# DIGITAL_40G_ACCELEROMETER_REV_1.net
KiCad netlist of a schematic drawn in EAGLE
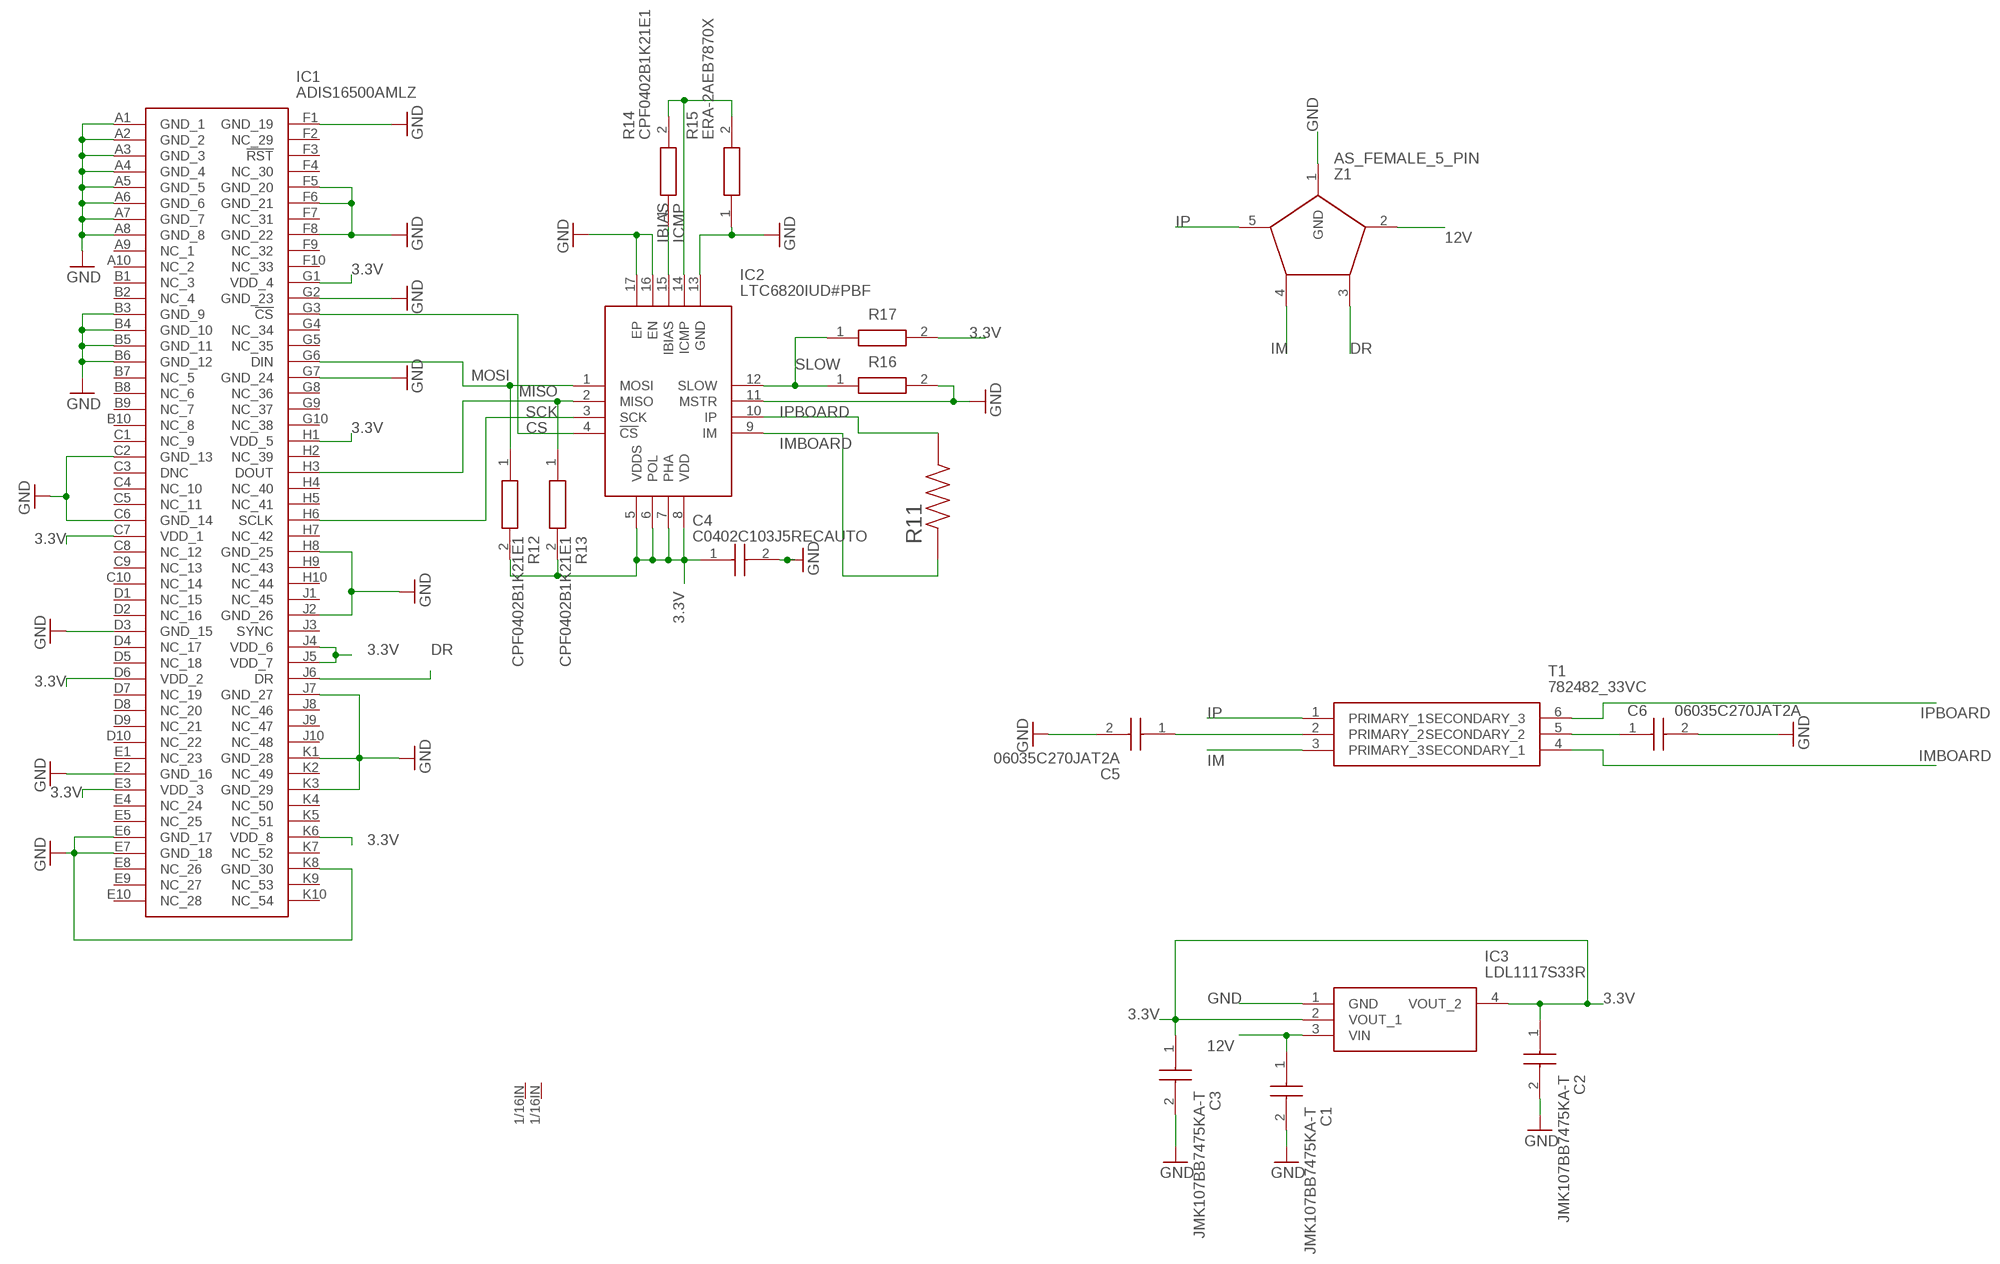
[diagram p0: schematic, sheet 1]

(export (version "E")
  (design (tool "Eeschema 10.0.6"))
  (components
    (comp (ref "C1")
      (value "JMK107BB7475KA-T")
      (footprint "eagle-import:CAPC1608X90N")
      (fields (field (name "MOUSER_PART_NUMBER") "963-JMK107BB7475KA-T"))
      (libsource (lib "eagle-import") (part "JMK107BB7475KA-T"))
    )
    (comp (ref "C2")
      (value "JMK107BB7475KA-T")
      (footprint "eagle-import:CAPC1608X90N")
      (fields (field (name "MOUSER_PART_NUMBER") "963-JMK107BB7475KA-T"))
      (libsource (lib "eagle-import") (part "JMK107BB7475KA-T"))
    )
    (comp (ref "C3")
      (value "JMK107BB7475KA-T")
      (footprint "eagle-import:CAPC1608X90N")
      (fields (field (name "MOUSER_PART_NUMBER") "963-JMK107BB7475KA-T"))
      (libsource (lib "eagle-import") (part "JMK107BB7475KA-T"))
    )
    (comp (ref "C4")
      (value "C0402C103J5RECAUTO")
      (footprint "eagle-import:CAPC1005X55N")
      (fields (field (name "MOUSER_PART_NUMBER") "80-C0402C103J5RECAUT"))
      (libsource (lib "eagle-import") (part "C0402C103J5RECAUTO"))
    )
    (comp (ref "C5")
      (value "06035C270JAT2A")
      (footprint "eagle-import:CAPC1608X90N")
      (libsource (lib "eagle-import") (part "06035C270JAT2A"))
    )
    (comp (ref "C6")
      (value "06035C270JAT2A")
      (footprint "eagle-import:CAPC1608X90N")
      (libsource (lib "eagle-import") (part "06035C270JAT2A"))
    )
    (comp (ref "IC1")
      (value "ADIS16500AMLZ")
      (footprint "eagle-import:BGA100C127P10X10_1500X1500X608")
      (fields (field (name "MOUSER_PART_NUMBER") "584-ADIS16500AMLZ"))
      (libsource (lib "eagle-import") (part "ADIS16500AMLZ"))
    )
    (comp (ref "IC2")
      (value "LTC6820IUD#PBF")
      (footprint "eagle-import:QFN50P300X300X80-17N")
      (fields (field (name "MOUSER_PART_NUMBER") "584-LTC6820IUD#PBF"))
      (libsource (lib "eagle-import") (part "LTC6820IUD#PBF"))
    )
    (comp (ref "IC3")
      (value "LDL1117S33R")
      (footprint "eagle-import:SOT230P700X180-4N")
      (fields (field (name "MOUSER_PART_NUMBER") "511-LDL1117S33R"))
      (libsource (lib "eagle-import") (part "LDL1117S33R"))
    )
    (comp (ref "R11")
      (value "100")
      (footprint "eagle-import:RESC1005X40N")
      (fields (field (name "MF") "Vishay") (field (name "MP") "TNPW0402100RBYEP"))
      (libsource (lib "eagle-import") (part "TNPW0402100RBYEP"))
    )
    (comp (ref "R12")
      (value "CPF0402B1K21E1")
      (footprint "eagle-import:RESC1005X35N")
      (libsource (lib "eagle-import") (part "CPF0402B1K21E1"))
    )
    (comp (ref "R13")
      (value "CPF0402B1K21E1")
      (footprint "eagle-import:RESC1005X35N")
      (libsource (lib "eagle-import") (part "CPF0402B1K21E1"))
    )
    (comp (ref "R14")
      (value "CPF0402B1K21E1")
      (footprint "eagle-import:RESC1005X35N")
      (libsource (lib "eagle-import") (part "CPF0402B1K21E1"))
    )
    (comp (ref "R15")
      (value "ERA-2AEB7870X")
      (footprint "eagle-import:ERA2AED122X")
      (libsource (lib "eagle-import") (part "ERA-2AEB7870X"))
    )
    (comp (ref "R16")
      (value "CRG0402ZR")
      (footprint "eagle-import:RESC1005X40N")
      (fields (field (name "MOUSER_PART_NUMBER") "279-CRG0402ZR"))
      (libsource (lib "eagle-import") (part "CRG0402ZR"))
    )
    (comp (ref "R17")
      (value "CRG0402ZR")
      (footprint "eagle-import:RESC1005X40N")
      (fields (field (name "MOUSER_PART_NUMBER") "279-CRG0402ZR"))
      (libsource (lib "eagle-import") (part "CRG0402ZR"))
    )
    (comp (ref "T1")
      (value "782482_33VC")
      (footprint "eagle-import:DIP1016W60P254L914H635Q6N")
      (fields
        (field (name "MANUFACTURER_PART_NUMBER") "782482/33VC")
        (field (name "MOUSER_PART_NUMBER") "580-782482/33VC")
      )
      (libsource (lib "eagle-import") (part "782482_33VC"))
    )
    (comp (ref "U$3")
      (value "THROUGH_HOLE")
      (footprint "eagle-import:1_16TH_BOLT")
      (libsource (lib "eagle-import") (part "THROUGH_HOLE"))
    )
    (comp (ref "U$4")
      (value "THROUGH_HOLE")
      (footprint "eagle-import:1_16TH_BOLT")
      (libsource (lib "eagle-import") (part "THROUGH_HOLE"))
    )
    (comp (ref "Z1")
      (value "AS_FEMALE_5_PIN")
      (footprint "eagle-import:AS_FEMALE_5_PIN")
      (libsource (lib "eagle-import") (part "AS_FEMALE_5_PIN"))
    )
  )
  (nets
    (net (code "1") (name "/3.3V") (class "Default")
      (node (ref "C2") (pin "1") (pinfunction "1_1") (pintype "bidirectional"))
      (node (ref "C3") (pin "1") (pinfunction "1_1") (pintype "bidirectional"))
      (node (ref "C4") (pin "1") (pinfunction "1_1") (pintype "bidirectional"))
      (node (ref "IC1") (pin "C7") (pinfunction "VDD_1_C7") (pintype "bidirectional"))
      (node (ref "IC1") (pin "D6") (pinfunction "VDD_2_D6") (pintype "bidirectional"))
      (node (ref "IC1") (pin "E3") (pinfunction "VDD_3_E3") (pintype "bidirectional"))
      (node (ref "IC1") (pin "G1") (pinfunction "VDD_4_G1") (pintype "bidirectional"))
      (node (ref "IC1") (pin "H1") (pinfunction "VDD_5_H1") (pintype "bidirectional"))
      (node (ref "IC1") (pin "J4") (pinfunction "VDD_6_J4") (pintype "bidirectional"))
      (node (ref "IC1") (pin "J5") (pinfunction "VDD_7_J5") (pintype "bidirectional"))
      (node (ref "IC1") (pin "K6") (pinfunction "VDD_8_K6") (pintype "bidirectional"))
      (node (ref "IC2") (pin "5") (pinfunction "VDDS_5") (pintype "bidirectional"))
      (node (ref "IC2") (pin "6") (pinfunction "POL_6") (pintype "bidirectional"))
      (node (ref "IC2") (pin "7") (pinfunction "PHA_7") (pintype "bidirectional"))
      (node (ref "IC2") (pin "8") (pinfunction "VDD_8") (pintype "bidirectional"))
      (node (ref "IC3") (pin "2") (pinfunction "VOUT_1_2") (pintype "output"))
      (node (ref "IC3") (pin "4") (pinfunction "VOUT_2_4") (pintype "output"))
      (node (ref "R12") (pin "2") (pinfunction "2_2") (pintype "bidirectional"))
      (node (ref "R13") (pin "2") (pinfunction "2_2") (pintype "bidirectional"))
      (node (ref "R17") (pin "2") (pinfunction "2_2") (pintype "bidirectional"))
    )
    (net (code "2") (name "/12V") (class "Default")
      (node (ref "C1") (pin "1") (pinfunction "1_1") (pintype "bidirectional"))
      (node (ref "IC3") (pin "3") (pinfunction "VIN_3") (pintype "input"))
      (node (ref "Z1") (pin "2") (pinfunction "1_2") (pintype "bidirectional"))
    )
    (net (code "3") (name "/CS") (class "Default")
      (node (ref "IC1") (pin "G3") (pinfunction "~{CS}_G3") (pintype "bidirectional"))
      (node (ref "IC2") (pin "4") (pinfunction "~{CS}_4") (pintype "bidirectional"))
    )
    (net (code "4") (name "/DR") (class "Default")
      (node (ref "IC1") (pin "J6") (pinfunction "DR_J6") (pintype "bidirectional"))
      (node (ref "Z1") (pin "3") (pinfunction "2_3") (pintype "bidirectional"))
    )
    (net (code "5") (name "/IBIAS") (class "Default")
      (node (ref "IC2") (pin "15") (pinfunction "IBIAS_15") (pintype "bidirectional"))
      (node (ref "R14") (pin "1") (pinfunction "1_1") (pintype "bidirectional"))
    )
    (net (code "6") (name "/ICMP") (class "Default")
      (node (ref "IC2") (pin "14") (pinfunction "ICMP_14") (pintype "bidirectional"))
      (node (ref "R14") (pin "2") (pinfunction "2_2") (pintype "bidirectional"))
      (node (ref "R15") (pin "2") (pinfunction "2_2") (pintype "bidirectional"))
    )
    (net (code "7") (name "/IM") (class "Default")
      (node (ref "T1") (pin "3") (pinfunction "PRIMARY_3_3") (pintype "bidirectional"))
      (node (ref "Z1") (pin "4") (pinfunction "3_4") (pintype "bidirectional"))
    )
    (net (code "8") (name "/IMBOARD") (class "Default")
      (node (ref "IC2") (pin "9") (pinfunction "IM_9") (pintype "bidirectional"))
      (node (ref "R11") (pin "1") (pinfunction "1_1") (pintype "passive"))
      (node (ref "T1") (pin "4") (pinfunction "SECONDARY_1_4") (pintype "bidirectional"))
    )
    (net (code "9") (name "/IP") (class "Default")
      (node (ref "T1") (pin "1") (pinfunction "PRIMARY_1_1") (pintype "bidirectional"))
      (node (ref "Z1") (pin "5") (pinfunction "4_5") (pintype "bidirectional"))
    )
    (net (code "10") (name "/IPBOARD") (class "Default")
      (node (ref "IC2") (pin "10") (pinfunction "IP_10") (pintype "bidirectional"))
      (node (ref "R11") (pin "2") (pinfunction "2_2") (pintype "passive"))
      (node (ref "T1") (pin "6") (pinfunction "SECONDARY_3_6") (pintype "bidirectional"))
    )
    (net (code "11") (name "/MISO") (class "Default")
      (node (ref "IC1") (pin "H3") (pinfunction "DOUT_H3") (pintype "bidirectional"))
      (node (ref "IC2") (pin "2") (pinfunction "MISO_2") (pintype "bidirectional"))
      (node (ref "R13") (pin "1") (pinfunction "1_1") (pintype "bidirectional"))
    )
    (net (code "12") (name "/MOSI") (class "Default")
      (node (ref "IC1") (pin "G6") (pinfunction "DIN_G6") (pintype "bidirectional"))
      (node (ref "IC2") (pin "1") (pinfunction "MOSI_1") (pintype "bidirectional"))
      (node (ref "R12") (pin "1") (pinfunction "1_1") (pintype "bidirectional"))
    )
    (net (code "13") (name "/SCK") (class "Default")
      (node (ref "IC1") (pin "H6") (pinfunction "SCLK_H6") (pintype "bidirectional"))
      (node (ref "IC2") (pin "3") (pinfunction "SCK_3") (pintype "bidirectional"))
    )
    (net (code "14") (name "/SLOW") (class "Default")
      (node (ref "IC2") (pin "12") (pinfunction "SLOW_12") (pintype "bidirectional"))
      (node (ref "R16") (pin "1") (pinfunction "1_1") (pintype "bidirectional"))
      (node (ref "R17") (pin "1") (pinfunction "1_1") (pintype "bidirectional"))
    )
    (net (code "15") (name "GND") (class "Default")
      (node (ref "C1") (pin "2") (pinfunction "2_2") (pintype "bidirectional"))
      (node (ref "C2") (pin "2") (pinfunction "2_2") (pintype "bidirectional"))
      (node (ref "C3") (pin "2") (pinfunction "2_2") (pintype "bidirectional"))
      (node (ref "C4") (pin "2") (pinfunction "2_2") (pintype "bidirectional"))
      (node (ref "C5") (pin "2") (pinfunction "2_2") (pintype "bidirectional"))
      (node (ref "C6") (pin "2") (pinfunction "2_2") (pintype "bidirectional"))
      (node (ref "IC1") (pin "A1") (pinfunction "GND_1_A1") (pintype "bidirectional"))
      (node (ref "IC1") (pin "A2") (pinfunction "GND_2_A2") (pintype "bidirectional"))
      (node (ref "IC1") (pin "A3") (pinfunction "GND_3_A3") (pintype "bidirectional"))
      (node (ref "IC1") (pin "A4") (pinfunction "GND_4_A4") (pintype "bidirectional"))
      (node (ref "IC1") (pin "A5") (pinfunction "GND_5_A5") (pintype "bidirectional"))
      (node (ref "IC1") (pin "A6") (pinfunction "GND_6_A6") (pintype "bidirectional"))
      (node (ref "IC1") (pin "A7") (pinfunction "GND_7_A7") (pintype "bidirectional"))
      (node (ref "IC1") (pin "A8") (pinfunction "GND_8_A8") (pintype "bidirectional"))
      (node (ref "IC1") (pin "B3") (pinfunction "GND_9_B3") (pintype "bidirectional"))
      (node (ref "IC1") (pin "B4") (pinfunction "GND_10_B4") (pintype "bidirectional"))
      (node (ref "IC1") (pin "B5") (pinfunction "GND_11_B5") (pintype "bidirectional"))
      (node (ref "IC1") (pin "B6") (pinfunction "GND_12_B6") (pintype "bidirectional"))
      (node (ref "IC1") (pin "C2") (pinfunction "GND_13_C2") (pintype "bidirectional"))
      (node (ref "IC1") (pin "C6") (pinfunction "GND_14_C6") (pintype "bidirectional"))
      (node (ref "IC1") (pin "D3") (pinfunction "GND_15_D3") (pintype "bidirectional"))
      (node (ref "IC1") (pin "E2") (pinfunction "GND_16_E2") (pintype "bidirectional"))
      (node (ref "IC1") (pin "E6") (pinfunction "GND_17_E6") (pintype "bidirectional"))
      (node (ref "IC1") (pin "E7") (pinfunction "GND_18_E7") (pintype "bidirectional"))
      (node (ref "IC1") (pin "F1") (pinfunction "GND_19_F1") (pintype "bidirectional"))
      (node (ref "IC1") (pin "F5") (pinfunction "GND_20_F5") (pintype "bidirectional"))
      (node (ref "IC1") (pin "F6") (pinfunction "GND_21_F6") (pintype "bidirectional"))
      (node (ref "IC1") (pin "F8") (pinfunction "GND_22_F8") (pintype "bidirectional"))
      (node (ref "IC1") (pin "G2") (pinfunction "GND_23_G2") (pintype "bidirectional"))
      (node (ref "IC1") (pin "G7") (pinfunction "GND_24_G7") (pintype "bidirectional"))
      (node (ref "IC1") (pin "H8") (pinfunction "GND_25_H8") (pintype "bidirectional"))
      (node (ref "IC1") (pin "J2") (pinfunction "GND_26_J2") (pintype "bidirectional"))
      (node (ref "IC1") (pin "J7") (pinfunction "GND_27_J7") (pintype "bidirectional"))
      (node (ref "IC1") (pin "K1") (pinfunction "GND_28_K1") (pintype "bidirectional"))
      (node (ref "IC1") (pin "K3") (pinfunction "GND_29_K3") (pintype "bidirectional"))
      (node (ref "IC1") (pin "K8") (pinfunction "GND_30_K8") (pintype "bidirectional"))
      (node (ref "IC2") (pin "11") (pinfunction "MSTR_11") (pintype "bidirectional"))
      (node (ref "IC2") (pin "13") (pinfunction "GND_13") (pintype "bidirectional"))
      (node (ref "IC2") (pin "16") (pinfunction "EN_16") (pintype "bidirectional"))
      (node (ref "IC2") (pin "17") (pinfunction "EP_17") (pintype "bidirectional"))
      (node (ref "IC3") (pin "1") (pinfunction "GND_1") (pintype "power_in"))
      (node (ref "R15") (pin "1") (pinfunction "1_1") (pintype "bidirectional"))
      (node (ref "R16") (pin "2") (pinfunction "2_2") (pintype "bidirectional"))
      (node (ref "Z1") (pin "1") (pinfunction "GND_1") (pintype "bidirectional"))
    )
    (net (code "16") (name "Net-(T1-PRIMARY_2)") (class "Default")
      (node (ref "C5") (pin "1") (pinfunction "1_1") (pintype "bidirectional"))
      (node (ref "T1") (pin "2") (pinfunction "PRIMARY_2_2") (pintype "bidirectional"))
    )
    (net (code "17") (name "Net-(T1-SECONDARY_2)") (class "Default")
      (node (ref "C6") (pin "1") (pinfunction "1_1") (pintype "bidirectional"))
      (node (ref "T1") (pin "5") (pinfunction "SECONDARY_2_5") (pintype "bidirectional"))
    )
    (net (code "18") (name "unconnected-(IC1-DNC-PadC3)") (class "Default")
      (node (ref "IC1") (pin "C3") (pinfunction "DNC_C3") (pintype "bidirectional"))
    )
    (net (code "19") (name "unconnected-(IC1-NC_1-PadA9)") (class "Default")
      (node (ref "IC1") (pin "A9") (pinfunction "NC_1_A9") (pintype "bidirectional"))
    )
    (net (code "20") (name "unconnected-(IC1-NC_2-PadA10)") (class "Default")
      (node (ref "IC1") (pin "A10") (pinfunction "NC_2_A10") (pintype "bidirectional"))
    )
    (net (code "21") (name "unconnected-(IC1-NC_3-PadB1)") (class "Default")
      (node (ref "IC1") (pin "B1") (pinfunction "NC_3_B1") (pintype "bidirectional"))
    )
    (net (code "22") (name "unconnected-(IC1-NC_4-PadB2)") (class "Default")
      (node (ref "IC1") (pin "B2") (pinfunction "NC_4_B2") (pintype "bidirectional"))
    )
    (net (code "23") (name "unconnected-(IC1-NC_5-PadB7)") (class "Default")
      (node (ref "IC1") (pin "B7") (pinfunction "NC_5_B7") (pintype "bidirectional"))
    )
    (net (code "24") (name "unconnected-(IC1-NC_6-PadB8)") (class "Default")
      (node (ref "IC1") (pin "B8") (pinfunction "NC_6_B8") (pintype "bidirectional"))
    )
    (net (code "25") (name "unconnected-(IC1-NC_7-PadB9)") (class "Default")
      (node (ref "IC1") (pin "B9") (pinfunction "NC_7_B9") (pintype "bidirectional"))
    )
    (net (code "26") (name "unconnected-(IC1-NC_8-PadB10)") (class "Default")
      (node (ref "IC1") (pin "B10") (pinfunction "NC_8_B10") (pintype "bidirectional"))
    )
    (net (code "27") (name "unconnected-(IC1-NC_9-PadC1)") (class "Default")
      (node (ref "IC1") (pin "C1") (pinfunction "NC_9_C1") (pintype "bidirectional"))
    )
    (net (code "28") (name "unconnected-(IC1-NC_10-PadC4)") (class "Default")
      (node (ref "IC1") (pin "C4") (pinfunction "NC_10_C4") (pintype "bidirectional"))
    )
    (net (code "29") (name "unconnected-(IC1-NC_11-PadC5)") (class "Default")
      (node (ref "IC1") (pin "C5") (pinfunction "NC_11_C5") (pintype "bidirectional"))
    )
    (net (code "30") (name "unconnected-(IC1-NC_12-PadC8)") (class "Default")
      (node (ref "IC1") (pin "C8") (pinfunction "NC_12_C8") (pintype "bidirectional"))
    )
    (net (code "31") (name "unconnected-(IC1-NC_13-PadC9)") (class "Default")
      (node (ref "IC1") (pin "C9") (pinfunction "NC_13_C9") (pintype "bidirectional"))
    )
    (net (code "32") (name "unconnected-(IC1-NC_14-PadC10)") (class "Default")
      (node (ref "IC1") (pin "C10") (pinfunction "NC_14_C10") (pintype "bidirectional"))
    )
    (net (code "33") (name "unconnected-(IC1-NC_15-PadD1)") (class "Default")
      (node (ref "IC1") (pin "D1") (pinfunction "NC_15_D1") (pintype "bidirectional"))
    )
    (net (code "34") (name "unconnected-(IC1-NC_16-PadD2)") (class "Default")
      (node (ref "IC1") (pin "D2") (pinfunction "NC_16_D2") (pintype "bidirectional"))
    )
    (net (code "35") (name "unconnected-(IC1-NC_17-PadD4)") (class "Default")
      (node (ref "IC1") (pin "D4") (pinfunction "NC_17_D4") (pintype "bidirectional"))
    )
    (net (code "36") (name "unconnected-(IC1-NC_18-PadD5)") (class "Default")
      (node (ref "IC1") (pin "D5") (pinfunction "NC_18_D5") (pintype "bidirectional"))
    )
    (net (code "37") (name "unconnected-(IC1-NC_19-PadD7)") (class "Default")
      (node (ref "IC1") (pin "D7") (pinfunction "NC_19_D7") (pintype "bidirectional"))
    )
    (net (code "38") (name "unconnected-(IC1-NC_20-PadD8)") (class "Default")
      (node (ref "IC1") (pin "D8") (pinfunction "NC_20_D8") (pintype "bidirectional"))
    )
    (net (code "39") (name "unconnected-(IC1-NC_21-PadD9)") (class "Default")
      (node (ref "IC1") (pin "D9") (pinfunction "NC_21_D9") (pintype "bidirectional"))
    )
    (net (code "40") (name "unconnected-(IC1-NC_22-PadD10)") (class "Default")
      (node (ref "IC1") (pin "D10") (pinfunction "NC_22_D10") (pintype "bidirectional"))
    )
    (net (code "41") (name "unconnected-(IC1-NC_23-PadE1)") (class "Default")
      (node (ref "IC1") (pin "E1") (pinfunction "NC_23_E1") (pintype "bidirectional"))
    )
    (net (code "42") (name "unconnected-(IC1-NC_24-PadE4)") (class "Default")
      (node (ref "IC1") (pin "E4") (pinfunction "NC_24_E4") (pintype "bidirectional"))
    )
    (net (code "43") (name "unconnected-(IC1-NC_25-PadE5)") (class "Default")
      (node (ref "IC1") (pin "E5") (pinfunction "NC_25_E5") (pintype "bidirectional"))
    )
    (net (code "44") (name "unconnected-(IC1-NC_26-PadE8)") (class "Default")
      (node (ref "IC1") (pin "E8") (pinfunction "NC_26_E8") (pintype "bidirectional"))
    )
    (net (code "45") (name "unconnected-(IC1-NC_27-PadE9)") (class "Default")
      (node (ref "IC1") (pin "E9") (pinfunction "NC_27_E9") (pintype "bidirectional"))
    )
    (net (code "46") (name "unconnected-(IC1-NC_28-PadE10)") (class "Default")
      (node (ref "IC1") (pin "E10") (pinfunction "NC_28_E10") (pintype "bidirectional"))
    )
    (net (code "47") (name "unconnected-(IC1-NC_29-PadF2)") (class "Default")
      (node (ref "IC1") (pin "F2") (pinfunction "NC_29_F2") (pintype "bidirectional"))
    )
    (net (code "48") (name "unconnected-(IC1-NC_30-PadF4)") (class "Default")
      (node (ref "IC1") (pin "F4") (pinfunction "NC_30_F4") (pintype "bidirectional"))
    )
    (net (code "49") (name "unconnected-(IC1-NC_31-PadF7)") (class "Default")
      (node (ref "IC1") (pin "F7") (pinfunction "NC_31_F7") (pintype "bidirectional"))
    )
    (net (code "50") (name "unconnected-(IC1-NC_32-PadF9)") (class "Default")
      (node (ref "IC1") (pin "F9") (pinfunction "NC_32_F9") (pintype "bidirectional"))
    )
    (net (code "51") (name "unconnected-(IC1-NC_33-PadF10)") (class "Default")
      (node (ref "IC1") (pin "F10") (pinfunction "NC_33_F10") (pintype "bidirectional"))
    )
    (net (code "52") (name "unconnected-(IC1-NC_34-PadG4)") (class "Default")
      (node (ref "IC1") (pin "G4") (pinfunction "NC_34_G4") (pintype "bidirectional"))
    )
    (net (code "53") (name "unconnected-(IC1-NC_35-PadG5)") (class "Default")
      (node (ref "IC1") (pin "G5") (pinfunction "NC_35_G5") (pintype "bidirectional"))
    )
    (net (code "54") (name "unconnected-(IC1-NC_36-PadG8)") (class "Default")
      (node (ref "IC1") (pin "G8") (pinfunction "NC_36_G8") (pintype "bidirectional"))
    )
    (net (code "55") (name "unconnected-(IC1-NC_37-PadG9)") (class "Default")
      (node (ref "IC1") (pin "G9") (pinfunction "NC_37_G9") (pintype "bidirectional"))
    )
    (net (code "56") (name "unconnected-(IC1-NC_38-PadG10)") (class "Default")
      (node (ref "IC1") (pin "G10") (pinfunction "NC_38_G10") (pintype "bidirectional"))
    )
    (net (code "57") (name "unconnected-(IC1-NC_39-PadH2)") (class "Default")
      (node (ref "IC1") (pin "H2") (pinfunction "NC_39_H2") (pintype "bidirectional"))
    )
    (net (code "58") (name "unconnected-(IC1-NC_40-PadH4)") (class "Default")
      (node (ref "IC1") (pin "H4") (pinfunction "NC_40_H4") (pintype "bidirectional"))
    )
    (net (code "59") (name "unconnected-(IC1-NC_41-PadH5)") (class "Default")
      (node (ref "IC1") (pin "H5") (pinfunction "NC_41_H5") (pintype "bidirectional"))
    )
    (net (code "60") (name "unconnected-(IC1-NC_42-PadH7)") (class "Default")
      (node (ref "IC1") (pin "H7") (pinfunction "NC_42_H7") (pintype "bidirectional"))
    )
    (net (code "61") (name "unconnected-(IC1-NC_43-PadH9)") (class "Default")
      (node (ref "IC1") (pin "H9") (pinfunction "NC_43_H9") (pintype "bidirectional"))
    )
    (net (code "62") (name "unconnected-(IC1-NC_44-PadH10)") (class "Default")
      (node (ref "IC1") (pin "H10") (pinfunction "NC_44_H10") (pintype "bidirectional"))
    )
    (net (code "63") (name "unconnected-(IC1-NC_45-PadJ1)") (class "Default")
      (node (ref "IC1") (pin "J1") (pinfunction "NC_45_J1") (pintype "bidirectional"))
    )
    (net (code "64") (name "unconnected-(IC1-NC_46-PadJ8)") (class "Default")
      (node (ref "IC1") (pin "J8") (pinfunction "NC_46_J8") (pintype "bidirectional"))
    )
    (net (code "65") (name "unconnected-(IC1-NC_47-PadJ9)") (class "Default")
      (node (ref "IC1") (pin "J9") (pinfunction "NC_47_J9") (pintype "bidirectional"))
    )
    (net (code "66") (name "unconnected-(IC1-NC_48-PadJ10)") (class "Default")
      (node (ref "IC1") (pin "J10") (pinfunction "NC_48_J10") (pintype "bidirectional"))
    )
    (net (code "67") (name "unconnected-(IC1-NC_49-PadK2)") (class "Default")
      (node (ref "IC1") (pin "K2") (pinfunction "NC_49_K2") (pintype "bidirectional"))
    )
    (net (code "68") (name "unconnected-(IC1-NC_50-PadK4)") (class "Default")
      (node (ref "IC1") (pin "K4") (pinfunction "NC_50_K4") (pintype "bidirectional"))
    )
    (net (code "69") (name "unconnected-(IC1-NC_51-PadK5)") (class "Default")
      (node (ref "IC1") (pin "K5") (pinfunction "NC_51_K5") (pintype "bidirectional"))
    )
    (net (code "70") (name "unconnected-(IC1-NC_52-PadK7)") (class "Default")
      (node (ref "IC1") (pin "K7") (pinfunction "NC_52_K7") (pintype "bidirectional"))
    )
    (net (code "71") (name "unconnected-(IC1-NC_53-PadK9)") (class "Default")
      (node (ref "IC1") (pin "K9") (pinfunction "NC_53_K9") (pintype "bidirectional"))
    )
    (net (code "72") (name "unconnected-(IC1-NC_54-PadK10)") (class "Default")
      (node (ref "IC1") (pin "K10") (pinfunction "NC_54_K10") (pintype "bidirectional"))
    )
    (net (code "73") (name "unconnected-(IC1-SYNC-PadJ3)") (class "Default")
      (node (ref "IC1") (pin "J3") (pinfunction "SYNC_J3") (pintype "bidirectional"))
    )
    (net (code "74") (name "unconnected-(IC1-~{RST}-PadF3)") (class "Default")
      (node (ref "IC1") (pin "F3") (pinfunction "~{RST}_F3") (pintype "bidirectional"))
    )
    (net (code "75") (name "unconnected-(U$3-THROUGH_HOLE-Pad1{slash}16IN)") (class "Default")
      (node (ref "U$3") (pin "1/16IN") (pinfunction "THROUGH_HOLE_1/16IN") (pintype "bidirectional"))
    )
    (net (code "76") (name "unconnected-(U$4-THROUGH_HOLE-Pad1{slash}16IN)") (class "Default")
      (node (ref "U$4") (pin "1/16IN") (pinfunction "THROUGH_HOLE_1/16IN") (pintype "bidirectional"))
    )
  )
)
